# NewFinalProj.net
KiCad netlist of a schematic drawn in Altium Designer
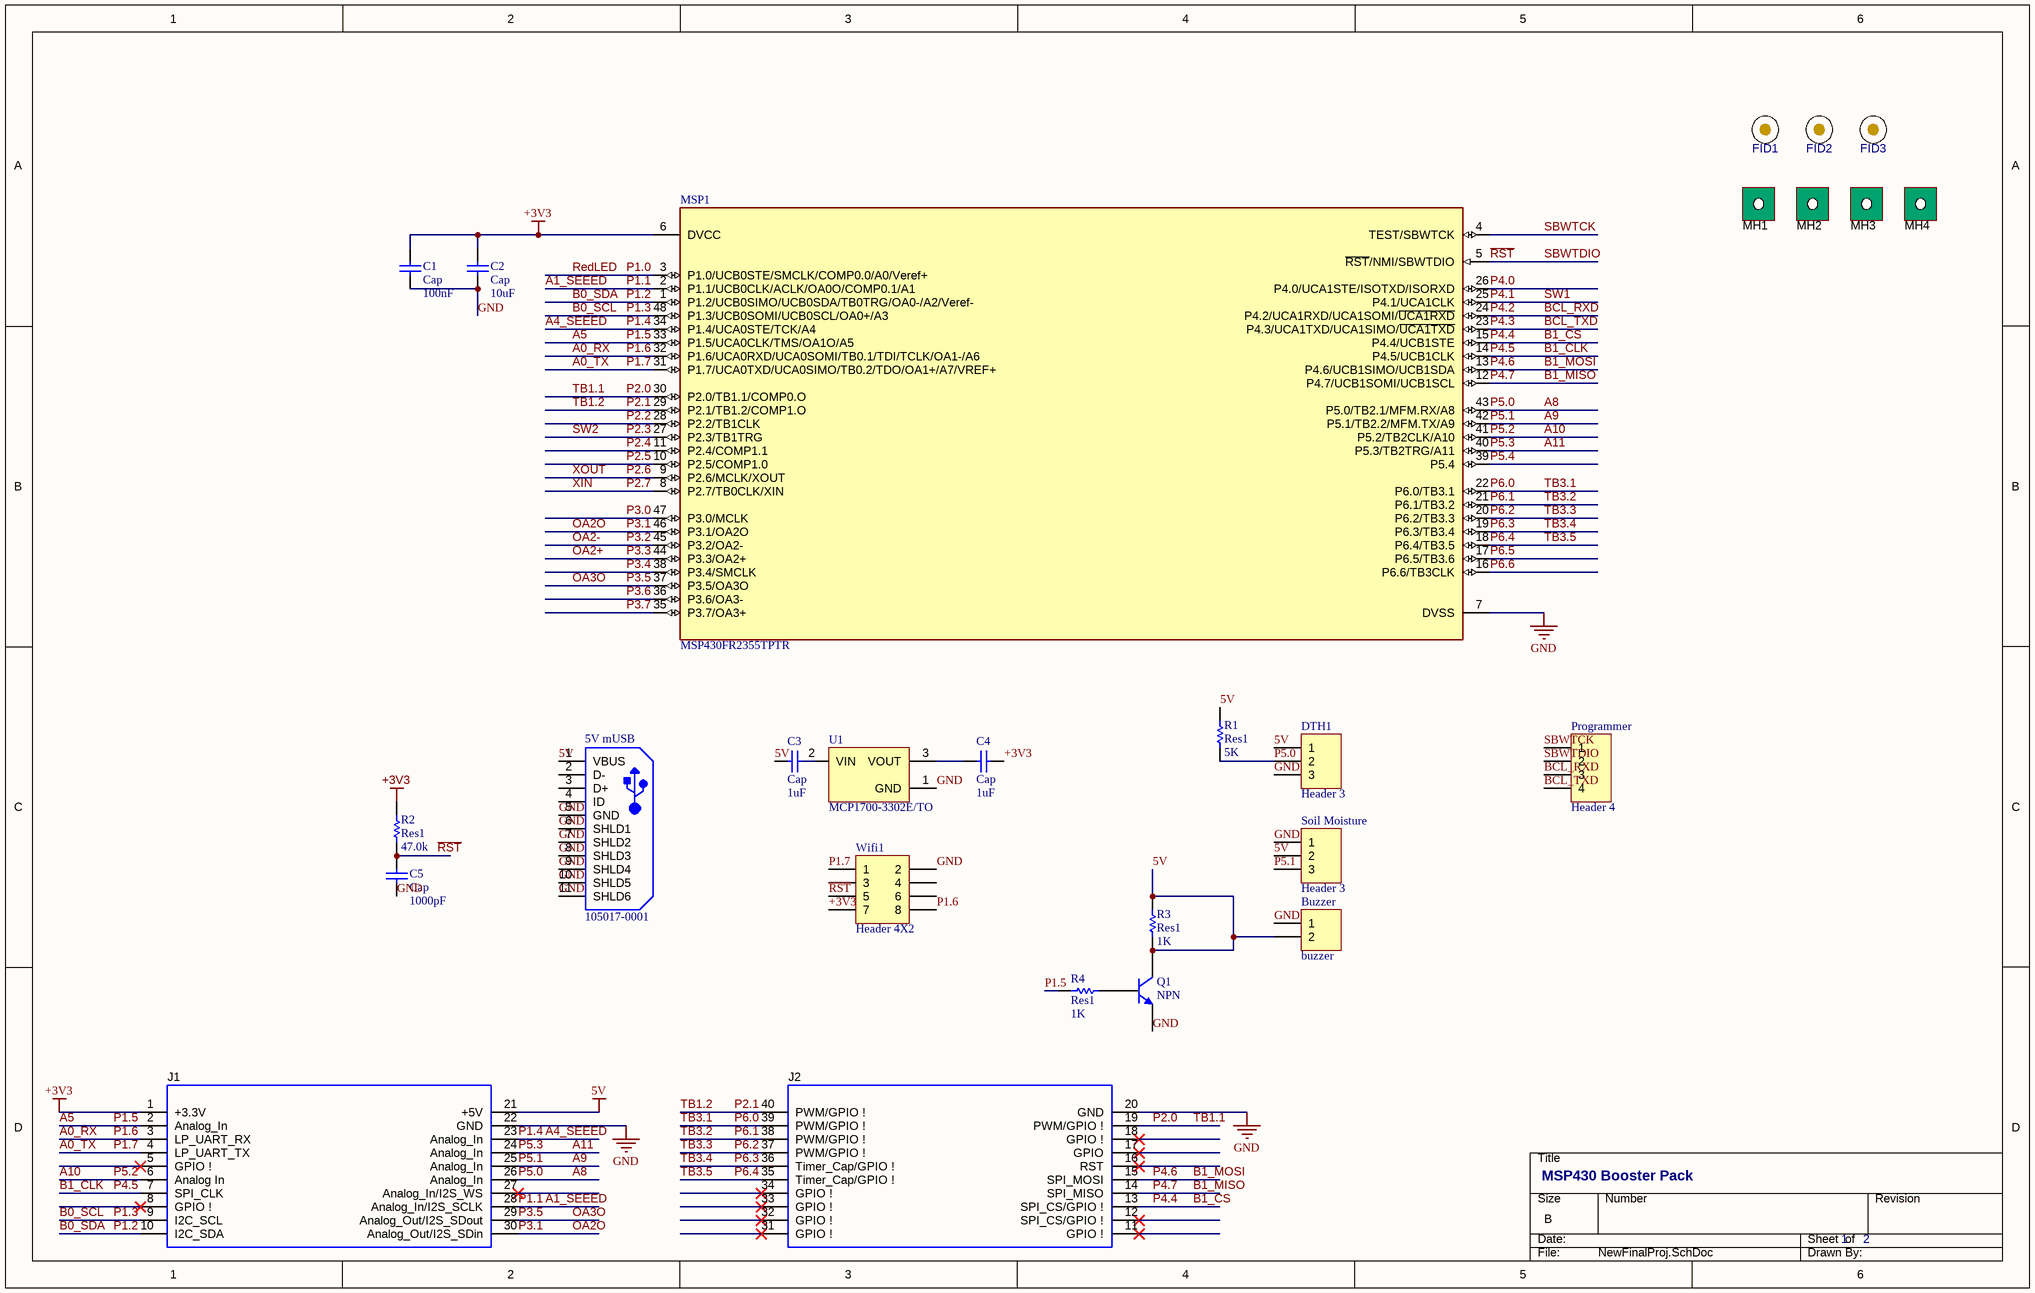
[diagram p0: NewFinalProj.SchDoc]

(export (version "E")
  (design (tool "Eeschema 10.0.6"))
  (components
    (comp (ref "5V mUSB")
      (value "105017-0001")
      (footprint "USB-MICRO-B_V")
      (fields (field (name "MANUFACTURER") "Molex"))
      (libsource (lib "Altium Content Vault") (part "USB-5-6SHLD"))
    )
    (comp (ref "Buzzer")
      (value "buzzer")
      (footprint "HDR1X2")
      (description "Header, 2-Pin")
      (fields (field (name "PUBLISHER") "Altium Limited"))
      (libsource (lib "Miscellaneous Connectors") (part "Header 2"))
    )
    (comp (ref "C1")
      (value "Cap")
      (footprint "RAD-0.3")
      (description "Capacitor")
      (fields (field (name "ALTIUM_VALUE") "100nF") (field (name "PUBLISHER") "Altium Limited"))
      (libsource (lib "Miscellaneous Devices") (part "Cap"))
    )
    (comp (ref "C2")
      (value "Cap")
      (footprint "RAD-0.3")
      (description "Capacitor")
      (fields (field (name "ALTIUM_VALUE") "10uF") (field (name "PUBLISHER") "Altium Limited"))
      (libsource (lib "Miscellaneous Devices") (part "Cap"))
    )
    (comp (ref "C3")
      (value "Cap")
      (footprint "RAD-0.3")
      (description "Capacitor")
      (fields (field (name "ALTIUM_VALUE") "1uF") (field (name "PUBLISHER") "Altium Limited"))
      (libsource (lib "Miscellaneous Devices") (part "Cap"))
    )
    (comp (ref "C4")
      (value "Cap")
      (footprint "RAD-0.3")
      (description "Capacitor")
      (fields (field (name "ALTIUM_VALUE") "1uF") (field (name "PUBLISHER") "Altium Limited"))
      (libsource (lib "Miscellaneous Devices") (part "Cap"))
    )
    (comp (ref "C5")
      (value "Cap")
      (footprint "RAD-0.3")
      (description "Capacitor")
      (fields (field (name "ALTIUM_VALUE") "1000pF") (field (name "PUBLISHER") "Altium Limited"))
      (libsource (lib "Miscellaneous Devices") (part "Cap"))
    )
    (comp (ref "DTH1")
      (value "Header 3")
      (footprint "HDR1X3")
      (description "Header, 3-Pin")
      (fields (field (name "PUBLISHER") "Altium Limited"))
      (libsource (lib "Miscellaneous Connectors") (part "Header 3"))
    )
    (comp (ref "FID1")
      (value "Fiducial")
      (footprint "Fiducial6.4-20")
      (description "Fiducial mark.  There is nothing to buy or mount.")
      (fields (field (name "SYMBOLCREATOR") "codlsc") (field (name "PUBLISHER") "Texas Instruments"))
      (libsource (lib "MiscParts") (part "Fiducial"))
    )
    (comp (ref "FID2")
      (value "Fiducial")
      (footprint "Fiducial6.4-20")
      (description "Fiducial mark.  There is nothing to buy or mount.")
      (fields (field (name "SYMBOLCREATOR") "codlsc") (field (name "PUBLISHER") "Texas Instruments"))
      (libsource (lib "MiscParts") (part "Fiducial"))
    )
    (comp (ref "FID3")
      (value "Fiducial")
      (footprint "Fiducial6.4-20")
      (description "Fiducial mark.  There is nothing to buy or mount.")
      (fields (field (name "SYMBOLCREATOR") "codlsc") (field (name "PUBLISHER") "Texas Instruments"))
      (libsource (lib "MiscParts") (part "Fiducial"))
    )
    (comp (ref "J1")
      (value "SSQ-110-03-T-D")
      (footprint "BoosterPack_40pin_J1J3")
      (description "Receptacle, 2.54mm, 10x2, Tin, TH")
      (fields
        (field (name "MANUFACTURER") "Samtec")
        (field (name "ALTERNATE PARTNUMBER") "CRD-081413-A-G")
        (field (name "SYMBOLCREATOR") "a0412235")
        (field (name "PUBLISHER") "Texas Instruments")
      )
      (libsource (lib "Hardware") (part "BoosterPack_40pin_J1J3"))
    )
    (comp (ref "J2")
      (value "SSQ-110-03-T-D")
      (footprint "BoosterPack_40pin_J2J4")
      (description "Receptacle, 2.54mm, 10x2, Tin, TH")
      (fields
        (field (name "MANUFACTURER") "Samtec")
        (field (name "ALTERNATE PARTNUMBER") "CRD-081413-A-G")
        (field (name "SYMBOLCREATOR") "a0412235")
        (field (name "PUBLISHER") "Texas Instruments")
      )
      (libsource (lib "Hardware") (part "BoosterPack_40pin_J2J4"))
    )
    (comp (ref "MH1")
      (value "MTG_NoPads")
      (footprint "NPTH125mil")
      (description "PCB Mounting Hole, No Pad")
      (fields
        (field (name "MANUFACTURER") "Any")
        (field (name "SYMBOLCREATOR") "a0412235")
        (field (name "PUBLISHER") "Texas Instruments")
      )
      (libsource (lib "Hardware") (part "Mounting Hole (non-standard) No Pad"))
    )
    (comp (ref "MH2")
      (value "MTG_NoPads")
      (footprint "NPTH125mil")
      (description "PCB Mounting Hole, No Pad")
      (fields
        (field (name "MANUFACTURER") "Any")
        (field (name "SYMBOLCREATOR") "a0412235")
        (field (name "PUBLISHER") "Texas Instruments")
      )
      (libsource (lib "Hardware") (part "Mounting Hole (non-standard) No Pad"))
    )
    (comp (ref "MH3")
      (value "MTG_NoPads")
      (footprint "NPTH125mil")
      (description "PCB Mounting Hole, No Pad")
      (fields
        (field (name "MANUFACTURER") "Any")
        (field (name "SYMBOLCREATOR") "a0412235")
        (field (name "PUBLISHER") "Texas Instruments")
      )
      (libsource (lib "Hardware") (part "Mounting Hole (non-standard) No Pad"))
    )
    (comp (ref "MH4")
      (value "MTG_NoPads")
      (footprint "NPTH125mil")
      (description "PCB Mounting Hole, No Pad")
      (fields
        (field (name "MANUFACTURER") "Any")
        (field (name "SYMBOLCREATOR") "a0412235")
        (field (name "PUBLISHER") "Texas Instruments")
      )
      (libsource (lib "Hardware") (part "Mounting Hole (non-standard) No Pad"))
    )
    (comp (ref "MSP1")
      (value "MSP430FR2355TPTR")
      (footprint "FP-PT0048A-MFG")
      (description "IC MCU 16BIT 32KB FRAM 48LQFP")
      (fields
        (field (name "MANUFACTURER") "Texas Instruments")
        (field (name "OCTOPART") "https://octopart.com/msp430fr2355tptr-texas+instruments-92191342")
      )
      (libsource (lib "Altium Content Vault") (part "bd983ca6877cdd146f198514b3acb3b"))
    )
    (comp (ref "Programmer")
      (value "Header 4")
      (footprint "HDR1X4")
      (description "Header, 4-Pin")
      (fields (field (name "PUBLISHER") "Altium Limited"))
      (libsource (lib "Miscellaneous Connectors") (part "Header 4"))
    )
    (comp (ref "Q1")
      (value "NPN")
      (footprint "TO-226-AA")
      (description "NPN Bipolar Transistor")
      (fields (field (name "PUBLISHER") "Altium Limited"))
      (libsource (lib "Miscellaneous Devices") (part "NPN"))
    )
    (comp (ref "R1")
      (value "Res1")
      (footprint "AXIAL-0.3")
      (description "Resistor")
      (fields (field (name "ALTIUM_VALUE") "5K") (field (name "PUBLISHER") "Altium Limited"))
      (libsource (lib "Miscellaneous Devices") (part "Res1"))
    )
    (comp (ref "R2")
      (value "Res1")
      (footprint "AXIAL-0.3")
      (description "Resistor")
      (fields (field (name "ALTIUM_VALUE") "47.0k") (field (name "PUBLISHER") "Altium Limited"))
      (libsource (lib "Miscellaneous Devices") (part "Res1"))
    )
    (comp (ref "R3")
      (value "Res1")
      (footprint "AXIAL-0.3")
      (description "Resistor")
      (fields (field (name "ALTIUM_VALUE") "1K") (field (name "PUBLISHER") "Altium Limited"))
      (libsource (lib "Miscellaneous Devices") (part "Res1"))
    )
    (comp (ref "R4")
      (value "Res1")
      (footprint "AXIAL-0.3")
      (description "Resistor")
      (fields (field (name "ALTIUM_VALUE") "1K") (field (name "PUBLISHER") "Altium Limited"))
      (libsource (lib "Miscellaneous Devices") (part "Res1"))
    )
    (comp (ref "Soil Moisture")
      (value "Header 3")
      (footprint "HDR1X3")
      (description "Header, 3-Pin")
      (fields (field (name "PUBLISHER") "Altium Limited"))
      (libsource (lib "Miscellaneous Connectors") (part "Header 3"))
    )
    (comp (ref "U1")
      (value "MCP1700-3302E/TO")
      (footprint "TO-92-TO3")
      (description "Low Quiescent Current LDO, 3-Pin TO-92, Extended TemperatureBAG")
      (libsource (lib "Altium Content Vault") (part "PM-LINEREG-MCP1700-IL3B"))
    )
    (comp (ref "Wifi1")
      (value "Header 4X2")
      (footprint "HDR2X4")
      (description "Header, 4-Pin, Dual row")
      (fields (field (name "PUBLISHER") "Altium Limited"))
      (libsource (lib "Miscellaneous Connectors") (part "Header 4X2"))
    )
  )
  (nets
    (net (code "1") (name "+3V3") (class "Default")
      (node (ref "C1") (pin "2") (pinfunction "2_2") (pintype "passive"))
      (node (ref "C2") (pin "2") (pinfunction "2_2") (pintype "passive"))
      (node (ref "C4") (pin "2") (pinfunction "2_2") (pintype "passive"))
      (node (ref "J1") (pin "1") (pinfunction "+3.3V_1") (pintype "power_in"))
      (node (ref "MSP1") (pin "6") (pinfunction "DVCC_6") (pintype "power_in"))
      (node (ref "R2") (pin "2") (pinfunction "2_2") (pintype "passive"))
      (node (ref "Wifi1") (pin "7") (pinfunction "7_7") (pintype "passive"))
    )
    (net (code "2") (name "/A0_RX") (class "Default")
      (node (ref "J1") (pin "3") (pinfunction "LP_UART_RX_3") (pintype "passive"))
      (node (ref "MSP1") (pin "32") (pinfunction "P1.6/UCA0RXD/UCA0SOMI/TB0.1/TDI/TCLK/OA1-/A6_32") (pintype "bidirectional"))
      (node (ref "Wifi1") (pin "8") (pinfunction "8_8") (pintype "passive"))
    )
    (net (code "3") (name "/A0_TX") (class "Default")
      (node (ref "J1") (pin "4") (pinfunction "LP_UART_TX_4") (pintype "passive"))
      (node (ref "MSP1") (pin "31") (pinfunction "P1.7/UCA0TXD/UCA0SIMO/TB0.2/TDO/OA1+/A7/VREF+_31") (pintype "bidirectional"))
      (node (ref "Wifi1") (pin "1") (pinfunction "1_1") (pintype "passive"))
    )
    (net (code "4") (name "/A1_SEEED") (class "Default")
      (node (ref "J1") (pin "28") (pinfunction "Analog_In/I2S_SCLK_28") (pintype "passive"))
      (node (ref "MSP1") (pin "2") (pinfunction "P1.1/UCB0CLK/ACLK/OA0O/COMP0.1/A1_2") (pintype "bidirectional"))
    )
    (net (code "5") (name "/A4_SEEED") (class "Default")
      (node (ref "J1") (pin "23") (pinfunction "Analog_In_23") (pintype "passive"))
      (node (ref "MSP1") (pin "34") (pinfunction "P1.4/UCA0STE/TCK/A4_34") (pintype "bidirectional"))
    )
    (net (code "6") (name "/A5") (class "Default")
      (node (ref "J1") (pin "2") (pinfunction "Analog_In_2") (pintype "passive"))
      (node (ref "MSP1") (pin "33") (pinfunction "P1.5/UCA0CLK/TMS/OA1O/A5_33") (pintype "bidirectional"))
      (node (ref "R4") (pin "1") (pinfunction "1_1") (pintype "passive"))
    )
    (net (code "7") (name "/A8") (class "Default")
      (node (ref "DTH1") (pin "2") (pinfunction "2_2") (pintype "passive"))
      (node (ref "J1") (pin "26") (pinfunction "Analog_In_26") (pintype "passive"))
      (node (ref "MSP1") (pin "43") (pinfunction "P5.0/TB2.1/MFM.RX/A8_43") (pintype "bidirectional"))
      (node (ref "R1") (pin "1") (pinfunction "1_1") (pintype "passive"))
    )
    (net (code "8") (name "/A9") (class "Default")
      (node (ref "J1") (pin "25") (pinfunction "Analog_In_25") (pintype "passive"))
      (node (ref "MSP1") (pin "42") (pinfunction "P5.1/TB2.2/MFM.TX/A9_42") (pintype "bidirectional"))
      (node (ref "Soil Moisture") (pin "3") (pinfunction "3_3") (pintype "passive"))
    )
    (net (code "9") (name "/A10") (class "Default")
      (node (ref "J1") (pin "6") (pinfunction "Analog_In_6") (pintype "passive"))
      (node (ref "MSP1") (pin "41") (pinfunction "P5.2/TB2CLK/A10_41") (pintype "bidirectional"))
    )
    (net (code "10") (name "/A11") (class "Default")
      (node (ref "J1") (pin "24") (pinfunction "Analog_In_24") (pintype "passive"))
      (node (ref "MSP1") (pin "40") (pinfunction "P5.3/TB2TRG/A11_40") (pintype "bidirectional"))
    )
    (net (code "11") (name "/B0_SCL") (class "Default")
      (node (ref "J1") (pin "9") (pinfunction "I2C_SCL_9") (pintype "passive"))
      (node (ref "MSP1") (pin "48") (pinfunction "P1.3/UCB0SOMI/UCB0SCL/OA0+/A3_48") (pintype "bidirectional"))
    )
    (net (code "12") (name "/B0_SDA") (class "Default")
      (node (ref "J1") (pin "10") (pinfunction "I2C_SDA_10") (pintype "passive"))
      (node (ref "MSP1") (pin "1") (pinfunction "P1.2/UCB0SIMO/UCB0SDA/TB0TRG/OA0-/A2/Veref-_1") (pintype "bidirectional"))
    )
    (net (code "13") (name "/B1_CLK") (class "Default")
      (node (ref "J1") (pin "7") (pinfunction "SPI_CLK_7") (pintype "passive"))
      (node (ref "MSP1") (pin "14") (pinfunction "P4.5/UCB1CLK_14") (pintype "bidirectional"))
    )
    (net (code "14") (name "/B1_CS") (class "Default")
      (node (ref "J2") (pin "13") (pinfunction "SPI_CS/GPIO_!_13") (pintype "passive"))
      (node (ref "MSP1") (pin "15") (pinfunction "P4.4/UCB1STE_15") (pintype "bidirectional"))
    )
    (net (code "15") (name "/B1_MISO") (class "Default")
      (node (ref "J2") (pin "14") (pinfunction "SPI_MISO_14") (pintype "passive"))
      (node (ref "MSP1") (pin "12") (pinfunction "P4.7/UCB1SOMI/UCB1SCL_12") (pintype "bidirectional"))
    )
    (net (code "16") (name "/B1_MOSI") (class "Default")
      (node (ref "J2") (pin "15") (pinfunction "SPI_MOSI_15") (pintype "passive"))
      (node (ref "MSP1") (pin "13") (pinfunction "P4.6/UCB1SIMO/UCB1SDA_13") (pintype "bidirectional"))
    )
    (net (code "17") (name "/BCL_RXD") (class "Default")
      (node (ref "MSP1") (pin "24") (pinfunction "P4.2/UCA1RXD/UCA1SOMI/~{UCA1RXD}_24") (pintype "bidirectional"))
      (node (ref "Programmer") (pin "3") (pinfunction "3_3") (pintype "passive"))
    )
    (net (code "18") (name "/BCL_TXD") (class "Default")
      (node (ref "MSP1") (pin "23") (pinfunction "P4.3/UCA1TXD/UCA1SIMO/~{UCA1TXD}_23") (pintype "bidirectional"))
      (node (ref "Programmer") (pin "4") (pinfunction "4_4") (pintype "passive"))
    )
    (net (code "19") (name "/OA2+") (class "Default")
      (node (ref "MSP1") (pin "44") (pinfunction "P3.3/OA2+_44") (pintype "bidirectional"))
    )
    (net (code "20") (name "/OA2-") (class "Default")
      (node (ref "MSP1") (pin "45") (pinfunction "P3.2/OA2-_45") (pintype "bidirectional"))
    )
    (net (code "21") (name "/OA2O") (class "Default")
      (node (ref "J1") (pin "30") (pinfunction "Analog_Out/I2S_SDin_30") (pintype "passive"))
      (node (ref "MSP1") (pin "46") (pinfunction "P3.1/OA2O_46") (pintype "bidirectional"))
    )
    (net (code "22") (name "/OA3O") (class "Default")
      (node (ref "J1") (pin "29") (pinfunction "Analog_Out/I2S_SDout_29") (pintype "passive"))
      (node (ref "MSP1") (pin "37") (pinfunction "P3.5/OA3O_37") (pintype "bidirectional"))
    )
    (net (code "23") (name "/P1.0") (class "Default")
      (node (ref "MSP1") (pin "3") (pinfunction "P1.0/UCB0STE/SMCLK/COMP0.0/A0/Veref+_3") (pintype "bidirectional"))
    )
    (net (code "24") (name "/P2.0") (class "Default")
      (node (ref "J2") (pin "19") (pinfunction "PWM/GPIO_!_19") (pintype "passive"))
      (node (ref "MSP1") (pin "30") (pinfunction "P2.0/TB1.1/COMP0.O_30") (pintype "bidirectional"))
    )
    (net (code "25") (name "/P2.1") (class "Default")
      (node (ref "J2") (pin "40") (pinfunction "PWM/GPIO_!_40") (pintype "passive"))
      (node (ref "MSP1") (pin "29") (pinfunction "P2.1/TB1.2/COMP1.O_29") (pintype "bidirectional"))
    )
    (net (code "26") (name "/P2.2") (class "Default")
      (node (ref "MSP1") (pin "28") (pinfunction "P2.2/TB1CLK_28") (pintype "bidirectional"))
    )
    (net (code "27") (name "/P2.3") (class "Default")
      (node (ref "MSP1") (pin "27") (pinfunction "P2.3/TB1TRG_27") (pintype "bidirectional"))
    )
    (net (code "28") (name "/P2.4") (class "Default")
      (node (ref "MSP1") (pin "11") (pinfunction "P2.4/COMP1.1_11") (pintype "bidirectional"))
    )
    (net (code "29") (name "/P2.5") (class "Default")
      (node (ref "MSP1") (pin "10") (pinfunction "P2.5/COMP1.0_10") (pintype "bidirectional"))
    )
    (net (code "30") (name "/P2.6") (class "Default")
      (node (ref "MSP1") (pin "9") (pinfunction "P2.6/MCLK/XOUT_9") (pintype "bidirectional"))
    )
    (net (code "31") (name "/P2.7") (class "Default")
      (node (ref "MSP1") (pin "8") (pinfunction "P2.7/TB0CLK/XIN_8") (pintype "bidirectional"))
    )
    (net (code "32") (name "/P3.0") (class "Default")
      (node (ref "MSP1") (pin "47") (pinfunction "P3.0/MCLK_47") (pintype "bidirectional"))
    )
    (net (code "33") (name "/P3.4") (class "Default")
      (node (ref "MSP1") (pin "38") (pinfunction "P3.4/SMCLK_38") (pintype "bidirectional"))
    )
    (net (code "34") (name "/P3.6") (class "Default")
      (node (ref "MSP1") (pin "36") (pinfunction "P3.6/OA3-_36") (pintype "bidirectional"))
    )
    (net (code "35") (name "/P3.7") (class "Default")
      (node (ref "MSP1") (pin "35") (pinfunction "P3.7/OA3+_35") (pintype "bidirectional"))
    )
    (net (code "36") (name "/P4.0") (class "Default")
      (node (ref "MSP1") (pin "26") (pinfunction "P4.0/UCA1STE/ISOTXD/ISORXD_26") (pintype "bidirectional"))
    )
    (net (code "37") (name "/P4.1") (class "Default")
      (node (ref "MSP1") (pin "25") (pinfunction "P4.1/UCA1CLK_25") (pintype "bidirectional"))
    )
    (net (code "38") (name "/P5.4") (class "Default")
      (node (ref "MSP1") (pin "39") (pinfunction "P5.4_39") (pintype "bidirectional"))
    )
    (net (code "39") (name "/P6.0") (class "Default")
      (node (ref "J2") (pin "39") (pinfunction "PWM/GPIO_!_39") (pintype "passive"))
      (node (ref "MSP1") (pin "22") (pinfunction "P6.0/TB3.1_22") (pintype "bidirectional"))
    )
    (net (code "40") (name "/P6.1") (class "Default")
      (node (ref "J2") (pin "38") (pinfunction "PWM/GPIO_!_38") (pintype "passive"))
      (node (ref "MSP1") (pin "21") (pinfunction "P6.1/TB3.2_21") (pintype "bidirectional"))
    )
    (net (code "41") (name "/P6.2") (class "Default")
      (node (ref "J2") (pin "37") (pinfunction "PWM/GPIO_!_37") (pintype "passive"))
      (node (ref "MSP1") (pin "20") (pinfunction "P6.2/TB3.3_20") (pintype "bidirectional"))
    )
    (net (code "42") (name "/P6.3") (class "Default")
      (node (ref "J2") (pin "36") (pinfunction "Timer_Cap/GPIO_!_36") (pintype "passive"))
      (node (ref "MSP1") (pin "19") (pinfunction "P6.3/TB3.4_19") (pintype "bidirectional"))
    )
    (net (code "43") (name "/P6.4") (class "Default")
      (node (ref "J2") (pin "35") (pinfunction "Timer_Cap/GPIO_!_35") (pintype "passive"))
      (node (ref "MSP1") (pin "18") (pinfunction "P6.4/TB3.5_18") (pintype "bidirectional"))
    )
    (net (code "44") (name "/P6.5") (class "Default")
      (node (ref "MSP1") (pin "17") (pinfunction "P6.5/TB3.6_17") (pintype "bidirectional"))
    )
    (net (code "45") (name "/P6.6") (class "Default")
      (node (ref "MSP1") (pin "16") (pinfunction "P6.6/TB3CLK_16") (pintype "bidirectional"))
    )
    (net (code "46") (name "/SBWTCK") (class "Default")
      (node (ref "MSP1") (pin "4") (pinfunction "TEST/SBWTCK_4") (pintype "bidirectional"))
      (node (ref "Programmer") (pin "1") (pinfunction "1_1") (pintype "passive"))
    )
    (net (code "47") (name "/SBWTDIO") (class "Default")
      (node (ref "C5") (pin "2") (pinfunction "2_2") (pintype "passive"))
      (node (ref "MSP1") (pin "5") (pinfunction "~{RST}/NMI/SBWTDIO_5") (pintype "input"))
      (node (ref "Programmer") (pin "2") (pinfunction "2_2") (pintype "passive"))
      (node (ref "R2") (pin "1") (pinfunction "1_1") (pintype "passive"))
      (node (ref "Wifi1") (pin "5") (pinfunction "5_5") (pintype "passive"))
    )
    (net (code "48") (name "5V") (class "Default")
      (node (ref "5V mUSB") (pin "1") (pinfunction "VBUS_1") (pintype "passive"))
      (node (ref "Buzzer") (pin "2") (pinfunction "2_2") (pintype "passive"))
      (node (ref "C3") (pin "1") (pinfunction "1_1") (pintype "passive"))
      (node (ref "DTH1") (pin "1") (pinfunction "1_1") (pintype "passive"))
      (node (ref "J1") (pin "21") (pinfunction "+5V_21") (pintype "power_in"))
      (node (ref "Q1") (pin "1") (pinfunction "C_1") (pintype "passive"))
      (node (ref "R1") (pin "2") (pinfunction "2_2") (pintype "passive"))
      (node (ref "R3") (pin "1") (pinfunction "1_1") (pintype "passive"))
      (node (ref "R3") (pin "2") (pinfunction "2_2") (pintype "passive"))
      (node (ref "Soil Moisture") (pin "2") (pinfunction "2_2") (pintype "passive"))
    )
    (net (code "49") (name "GND") (class "Default")
      (node (ref "5V mUSB") (pin "10") (pinfunction "SHLD5_10") (pintype "passive"))
      (node (ref "5V mUSB") (pin "11") (pinfunction "SHLD6_11") (pintype "passive"))
      (node (ref "5V mUSB") (pin "5") (pinfunction "GND_5") (pintype "passive"))
      (node (ref "5V mUSB") (pin "6") (pinfunction "SHLD1_6") (pintype "passive"))
      (node (ref "5V mUSB") (pin "7") (pinfunction "SHLD2_7") (pintype "passive"))
      (node (ref "5V mUSB") (pin "8") (pinfunction "SHLD3_8") (pintype "passive"))
      (node (ref "5V mUSB") (pin "9") (pinfunction "SHLD4_9") (pintype "passive"))
      (node (ref "Buzzer") (pin "1") (pinfunction "1_1") (pintype "passive"))
      (node (ref "C1") (pin "1") (pinfunction "1_1") (pintype "passive"))
      (node (ref "C2") (pin "1") (pinfunction "1_1") (pintype "passive"))
      (node (ref "C5") (pin "1") (pinfunction "1_1") (pintype "passive"))
      (node (ref "DTH1") (pin "3") (pinfunction "3_3") (pintype "passive"))
      (node (ref "J1") (pin "22") (pinfunction "GND_22") (pintype "power_in"))
      (node (ref "J2") (pin "20") (pinfunction "GND_20") (pintype "power_in"))
      (node (ref "MSP1") (pin "7") (pinfunction "DVSS_7") (pintype "power_in"))
      (node (ref "Q1") (pin "3") (pinfunction "E_3") (pintype "passive"))
      (node (ref "Soil Moisture") (pin "1") (pinfunction "1_1") (pintype "passive"))
      (node (ref "U1") (pin "1") (pinfunction "GND_1") (pintype "power_in"))
      (node (ref "Wifi1") (pin "2") (pinfunction "2_2") (pintype "passive"))
    )
    (net (code "50") (name "Net-(Q1-B)") (class "Default")
      (node (ref "Q1") (pin "2") (pinfunction "B_2") (pintype "passive"))
      (node (ref "R4") (pin "2") (pinfunction "2_2") (pintype "passive"))
    )
    (net (code "51") (name "Net-(U1-VIN)") (class "Default")
      (node (ref "C3") (pin "2") (pinfunction "2_2") (pintype "passive"))
      (node (ref "U1") (pin "2") (pinfunction "VIN_2") (pintype "power_in"))
    )
    (net (code "52") (name "Net-(U1-VOUT)") (class "Default")
      (node (ref "C4") (pin "1") (pinfunction "1_1") (pintype "passive"))
      (node (ref "U1") (pin "3") (pinfunction "VOUT_3") (pintype "power_in"))
    )
    (net (code "53") (name "unconnected-(5V mUSB-D+-Pad3)") (class "Default")
      (node (ref "5V mUSB") (pin "3") (pinfunction "D+_3") (pintype "passive"))
    )
    (net (code "54") (name "unconnected-(5V mUSB-D--Pad2)") (class "Default")
      (node (ref "5V mUSB") (pin "2") (pinfunction "D-_2") (pintype "passive"))
    )
    (net (code "55") (name "unconnected-(5V mUSB-ID-Pad4)") (class "Default")
      (node (ref "5V mUSB") (pin "4") (pinfunction "ID_4") (pintype "passive"))
    )
    (net (code "56") (name "unconnected-(J1-Analog_In{slash}I2S_WS-Pad27)") (class "Default")
      (node (ref "J1") (pin "27") (pinfunction "Analog_In/I2S_WS_27") (pintype "passive+no_connect"))
    )
    (net (code "57") (name "unconnected-(J1-GPIO_!-Pad5)") (class "Default")
      (node (ref "J1") (pin "5") (pinfunction "GPIO_!_5") (pintype "passive+no_connect"))
    )
    (net (code "58") (name "unconnected-(J1-GPIO_!-Pad8)") (class "Default")
      (node (ref "J1") (pin "8") (pinfunction "GPIO_!_8") (pintype "passive+no_connect"))
    )
    (net (code "59") (name "unconnected-(J2-GPIO-Pad17)") (class "Default")
      (node (ref "J2") (pin "17") (pinfunction "GPIO_17") (pintype "passive+no_connect"))
    )
    (net (code "60") (name "unconnected-(J2-GPIO_!-Pad11)") (class "Default")
      (node (ref "J2") (pin "11") (pinfunction "GPIO_!_11") (pintype "passive+no_connect"))
    )
    (net (code "61") (name "unconnected-(J2-GPIO_!-Pad18)") (class "Default")
      (node (ref "J2") (pin "18") (pinfunction "GPIO_!_18") (pintype "passive+no_connect"))
    )
    (net (code "62") (name "unconnected-(J2-GPIO_!-Pad31)") (class "Default")
      (node (ref "J2") (pin "31") (pinfunction "GPIO_!_31") (pintype "passive+no_connect"))
    )
    (net (code "63") (name "unconnected-(J2-GPIO_!-Pad32)") (class "Default")
      (node (ref "J2") (pin "32") (pinfunction "GPIO_!_32") (pintype "passive+no_connect"))
    )
    (net (code "64") (name "unconnected-(J2-GPIO_!-Pad33)") (class "Default")
      (node (ref "J2") (pin "33") (pinfunction "GPIO_!_33") (pintype "passive+no_connect"))
    )
    (net (code "65") (name "unconnected-(J2-GPIO_!-Pad34)") (class "Default")
      (node (ref "J2") (pin "34") (pinfunction "GPIO_!_34") (pintype "passive+no_connect"))
    )
    (net (code "66") (name "unconnected-(J2-RST-Pad16)") (class "Default")
      (node (ref "J2") (pin "16") (pinfunction "RST_16") (pintype "passive+no_connect"))
    )
    (net (code "67") (name "unconnected-(J2-SPI_CS{slash}GPIO_!-Pad12)") (class "Default")
      (node (ref "J2") (pin "12") (pinfunction "SPI_CS/GPIO_!_12") (pintype "passive+no_connect"))
    )
    (net (code "68") (name "unconnected-(Wifi1-Pad3)") (class "Default")
      (node (ref "Wifi1") (pin "3") (pinfunction "3_3") (pintype "passive"))
    )
    (net (code "69") (name "unconnected-(Wifi1-Pad4)") (class "Default")
      (node (ref "Wifi1") (pin "4") (pinfunction "4_4") (pintype "passive"))
    )
    (net (code "70") (name "unconnected-(Wifi1-Pad6)") (class "Default")
      (node (ref "Wifi1") (pin "6") (pinfunction "6_6") (pintype "passive"))
    )
  )
)
